# LEDStripCombiner.net
KiCad netlist of a schematic drawn in EAGLE
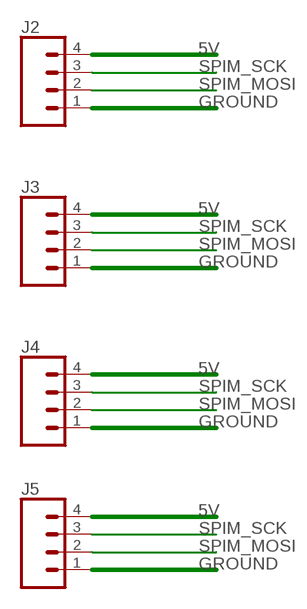
[diagram p0: schematic, sheet 1]

(export (version "E")
  (design (tool "Eeschema 10.0.6"))
  (components
    (comp (ref "J2")
      (value "CONN_041X04_NO_SILK")
      (footprint "eagle-import:1X04_NO_SILK")
      (libsource (lib "eagle-import") (part "CONN_041X04_NO_SILK"))
    )
    (comp (ref "J3")
      (value "CONN_041X04_NO_SILK")
      (footprint "eagle-import:1X04_NO_SILK")
      (libsource (lib "eagle-import") (part "CONN_041X04_NO_SILK"))
    )
    (comp (ref "J4")
      (value "CONN_041X04_NO_SILK")
      (footprint "eagle-import:1X04_NO_SILK")
      (libsource (lib "eagle-import") (part "CONN_041X04_NO_SILK"))
    )
    (comp (ref "J5")
      (value "CONN_041X04_NO_SILK")
      (footprint "eagle-import:1X04_NO_SILK")
      (libsource (lib "eagle-import") (part "CONN_041X04_NO_SILK"))
    )
  )
  (nets
    (net (code "1") (name "/5V") (class "Default")
      (node (ref "J2") (pin "4") (pinfunction "4_4") (pintype "passive"))
      (node (ref "J3") (pin "4") (pinfunction "4_4") (pintype "passive"))
      (node (ref "J4") (pin "4") (pinfunction "4_4") (pintype "passive"))
      (node (ref "J5") (pin "4") (pinfunction "4_4") (pintype "passive"))
    )
    (net (code "2") (name "/GROUND") (class "Default")
      (node (ref "J2") (pin "1") (pinfunction "1_1") (pintype "passive"))
      (node (ref "J3") (pin "1") (pinfunction "1_1") (pintype "passive"))
      (node (ref "J4") (pin "1") (pinfunction "1_1") (pintype "passive"))
      (node (ref "J5") (pin "1") (pinfunction "1_1") (pintype "passive"))
    )
    (net (code "3") (name "/SPIM_MOSI") (class "Default")
      (node (ref "J2") (pin "2") (pinfunction "2_2") (pintype "passive"))
      (node (ref "J3") (pin "2") (pinfunction "2_2") (pintype "passive"))
      (node (ref "J4") (pin "2") (pinfunction "2_2") (pintype "passive"))
      (node (ref "J5") (pin "2") (pinfunction "2_2") (pintype "passive"))
    )
    (net (code "4") (name "/SPIM_SCK") (class "Default")
      (node (ref "J2") (pin "3") (pinfunction "3_3") (pintype "passive"))
      (node (ref "J3") (pin "3") (pinfunction "3_3") (pintype "passive"))
      (node (ref "J4") (pin "3") (pinfunction "3_3") (pintype "passive"))
      (node (ref "J5") (pin "3") (pinfunction "3_3") (pintype "passive"))
    )
  )
)
